# DummyLoad_Frontpanel.net
KiCad netlist of a schematic drawn in EAGLE
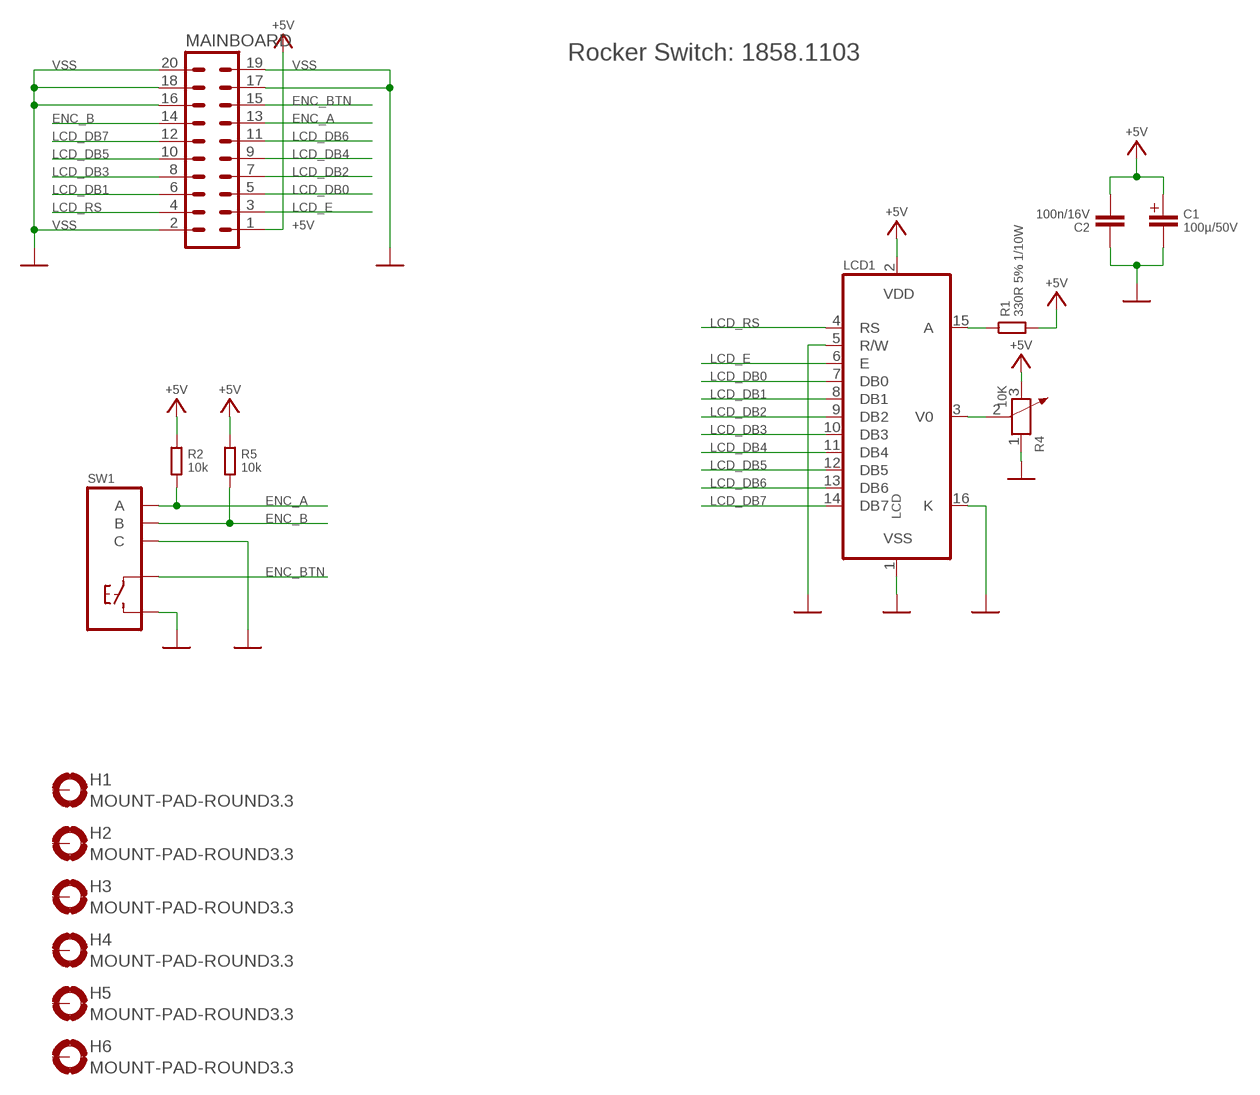
[diagram p0: schematic, sheet 1]

(export (version "E")
  (design (tool "Eeschema 10.0.6"))
  (components
    (comp (ref "C1")
      (value "100µ/50V")
      (footprint "eagle-import:C+_3.5_8")
      (libsource (lib "eagle-import") (part "C+3.5/8"))
    )
    (comp (ref "C2")
      (value "100n/16V")
      (footprint "eagle-import:0805")
      (libsource (lib "eagle-import") (part "CC/0805"))
    )
    (comp (ref "H1")
      (value "MOUNT-PAD-ROUND3.3")
      (footprint "eagle-import:3,3-PAD")
      (libsource (lib "eagle-import") (part "MOUNT-PAD-ROUND3.3"))
    )
    (comp (ref "H2")
      (value "MOUNT-PAD-ROUND3.3")
      (footprint "eagle-import:3,3-PAD")
      (libsource (lib "eagle-import") (part "MOUNT-PAD-ROUND3.3"))
    )
    (comp (ref "H3")
      (value "MOUNT-PAD-ROUND3.3")
      (footprint "eagle-import:3,3-PAD")
      (libsource (lib "eagle-import") (part "MOUNT-PAD-ROUND3.3"))
    )
    (comp (ref "H4")
      (value "MOUNT-PAD-ROUND3.3")
      (footprint "eagle-import:3,3-PAD")
      (libsource (lib "eagle-import") (part "MOUNT-PAD-ROUND3.3"))
    )
    (comp (ref "H5")
      (value "MOUNT-PAD-ROUND3.3")
      (footprint "eagle-import:3,3-PAD")
      (libsource (lib "eagle-import") (part "MOUNT-PAD-ROUND3.3"))
    )
    (comp (ref "H6")
      (value "MOUNT-PAD-ROUND3.3")
      (footprint "eagle-import:3,3-PAD")
      (libsource (lib "eagle-import") (part "MOUNT-PAD-ROUND3.3"))
    )
    (comp (ref "LCD1")
      (value "LCD")
      (footprint "eagle-import:DISPLAYTECH-204C")
      (libsource (lib "eagle-import") (part "LCD"))
    )
    (comp (ref "MAINBOARD")
      (value "MA10-2")
      (footprint "eagle-import:MA10-2")
      (libsource (lib "eagle-import") (part "MA10-2"))
    )
    (comp (ref "R1")
      (value "330R 5% 1/10W")
      (footprint "eagle-import:C0805K")
      (libsource (lib "eagle-import") (part "R-SMD0805"))
    )
    (comp (ref "R2")
      (value "10k")
      (footprint "eagle-import:C0805K")
      (libsource (lib "eagle-import") (part "R-SMD0805"))
    )
    (comp (ref "R4")
      (value "10K")
      (footprint "eagle-import:ADJR3-7.0X7.0X5.0MM")
      (fields (field (name "MPN") "SX3362P"))
      (libsource (lib "eagle-import") (part "TRIMPOT"))
    )
    (comp (ref "R5")
      (value "10k")
      (footprint "eagle-import:C0805K")
      (libsource (lib "eagle-import") (part "R-SMD0805"))
    )
    (comp (ref "SW1")
      (value "EC12E-SW")
      (footprint "eagle-import:EC12E-SW")
      (libsource (lib "eagle-import") (part "EC12E-SW"))
    )
  )
  (nets
    (net (code "1") (name "+5V") (class "Default")
      (node (ref "C1") (pin "+") (pinfunction "+_+") (pintype "passive"))
      (node (ref "C2") (pin "2") (pinfunction "2_2") (pintype "passive"))
      (node (ref "LCD1") (pin "2") (pinfunction "VDD_2") (pintype "power_in"))
      (node (ref "MAINBOARD") (pin "1") (pinfunction "1_1") (pintype "passive"))
      (node (ref "R1") (pin "2") (pinfunction "2_2") (pintype "passive"))
      (node (ref "R2") (pin "1") (pinfunction "1_1") (pintype "passive"))
      (node (ref "R4") (pin "3") (pinfunction "3_3") (pintype "passive"))
      (node (ref "R5") (pin "1") (pinfunction "1_1") (pintype "passive"))
    )
    (net (code "2") (name "/ENC_A") (class "Default")
      (node (ref "MAINBOARD") (pin "13") (pinfunction "13_13") (pintype "passive"))
      (node (ref "R2") (pin "2") (pinfunction "2_2") (pintype "passive"))
      (node (ref "SW1") (pin "A") (pinfunction "A_A") (pintype "passive"))
    )
    (net (code "3") (name "/ENC_B") (class "Default")
      (node (ref "MAINBOARD") (pin "14") (pinfunction "14_14") (pintype "passive"))
      (node (ref "R5") (pin "2") (pinfunction "2_2") (pintype "passive"))
      (node (ref "SW1") (pin "B") (pinfunction "B_B") (pintype "passive"))
    )
    (net (code "4") (name "/ENC_BTN") (class "Default")
      (node (ref "MAINBOARD") (pin "15") (pinfunction "15_15") (pintype "passive"))
      (node (ref "SW1") (pin "1") (pinfunction "1_1") (pintype "passive"))
    )
    (net (code "5") (name "/LCD_DB0") (class "Default")
      (node (ref "LCD1") (pin "7") (pinfunction "DB0_7") (pintype "passive"))
      (node (ref "MAINBOARD") (pin "5") (pinfunction "5_5") (pintype "passive"))
    )
    (net (code "6") (name "/LCD_DB1") (class "Default")
      (node (ref "LCD1") (pin "8") (pinfunction "DB1_8") (pintype "passive"))
      (node (ref "MAINBOARD") (pin "6") (pinfunction "6_6") (pintype "passive"))
    )
    (net (code "7") (name "/LCD_DB2") (class "Default")
      (node (ref "LCD1") (pin "9") (pinfunction "DB2_9") (pintype "passive"))
      (node (ref "MAINBOARD") (pin "7") (pinfunction "7_7") (pintype "passive"))
    )
    (net (code "8") (name "/LCD_DB3") (class "Default")
      (node (ref "LCD1") (pin "10") (pinfunction "DB3_10") (pintype "passive"))
      (node (ref "MAINBOARD") (pin "8") (pinfunction "8_8") (pintype "passive"))
    )
    (net (code "9") (name "/LCD_DB4") (class "Default")
      (node (ref "LCD1") (pin "11") (pinfunction "DB4_11") (pintype "passive"))
      (node (ref "MAINBOARD") (pin "9") (pinfunction "9_9") (pintype "passive"))
    )
    (net (code "10") (name "/LCD_DB5") (class "Default")
      (node (ref "LCD1") (pin "12") (pinfunction "DB5_12") (pintype "passive"))
      (node (ref "MAINBOARD") (pin "10") (pinfunction "10_10") (pintype "passive"))
    )
    (net (code "11") (name "/LCD_DB6") (class "Default")
      (node (ref "LCD1") (pin "13") (pinfunction "DB6_13") (pintype "passive"))
      (node (ref "MAINBOARD") (pin "11") (pinfunction "11_11") (pintype "passive"))
    )
    (net (code "12") (name "/LCD_DB7") (class "Default")
      (node (ref "LCD1") (pin "14") (pinfunction "DB7_14") (pintype "passive"))
      (node (ref "MAINBOARD") (pin "12") (pinfunction "12_12") (pintype "passive"))
    )
    (net (code "13") (name "/LCD_E") (class "Default")
      (node (ref "LCD1") (pin "6") (pinfunction "E_6") (pintype "passive"))
      (node (ref "MAINBOARD") (pin "3") (pinfunction "3_3") (pintype "passive"))
    )
    (net (code "14") (name "/LCD_RS") (class "Default")
      (node (ref "LCD1") (pin "4") (pinfunction "RS_4") (pintype "passive"))
      (node (ref "MAINBOARD") (pin "4") (pinfunction "4_4") (pintype "passive"))
    )
    (net (code "15") (name "Net-(LCD1-A)") (class "Default")
      (node (ref "LCD1") (pin "15") (pinfunction "A_15") (pintype "passive"))
      (node (ref "R1") (pin "1") (pinfunction "1_1") (pintype "passive"))
    )
    (net (code "16") (name "Net-(LCD1-V0)") (class "Default")
      (node (ref "LCD1") (pin "3") (pinfunction "V0_3") (pintype "passive"))
      (node (ref "R4") (pin "2") (pinfunction "2_2") (pintype "passive"))
    )
    (net (code "17") (name "VSS") (class "Default")
      (node (ref "C1") (pin "-") (pinfunction "-_-") (pintype "passive"))
      (node (ref "C2") (pin "1") (pinfunction "1_1") (pintype "passive"))
      (node (ref "LCD1") (pin "1") (pinfunction "VSS_1") (pintype "power_in"))
      (node (ref "LCD1") (pin "16") (pinfunction "K_16") (pintype "passive"))
      (node (ref "LCD1") (pin "5") (pinfunction "R/W_5") (pintype "passive"))
      (node (ref "MAINBOARD") (pin "16") (pinfunction "16_16") (pintype "passive"))
      (node (ref "MAINBOARD") (pin "17") (pinfunction "17_17") (pintype "passive"))
      (node (ref "MAINBOARD") (pin "18") (pinfunction "18_18") (pintype "passive"))
      (node (ref "MAINBOARD") (pin "19") (pinfunction "19_19") (pintype "passive"))
      (node (ref "MAINBOARD") (pin "2") (pinfunction "2_2") (pintype "passive"))
      (node (ref "MAINBOARD") (pin "20") (pinfunction "20_20") (pintype "passive"))
      (node (ref "R4") (pin "1") (pinfunction "1_1") (pintype "passive"))
      (node (ref "SW1") (pin "2") (pinfunction "2_2") (pintype "passive"))
      (node (ref "SW1") (pin "C") (pinfunction "C_C") (pintype "passive"))
    )
    (net (code "18") (name "unconnected-(H1-MOUNT-PadB3,3)") (class "Default")
      (node (ref "H1") (pin "B3,3") (pinfunction "MOUNT_B3,3") (pintype "passive"))
    )
    (net (code "19") (name "unconnected-(H2-MOUNT-PadB3,3)") (class "Default")
      (node (ref "H2") (pin "B3,3") (pinfunction "MOUNT_B3,3") (pintype "passive"))
    )
    (net (code "20") (name "unconnected-(H3-MOUNT-PadB3,3)") (class "Default")
      (node (ref "H3") (pin "B3,3") (pinfunction "MOUNT_B3,3") (pintype "passive"))
    )
    (net (code "21") (name "unconnected-(H4-MOUNT-PadB3,3)") (class "Default")
      (node (ref "H4") (pin "B3,3") (pinfunction "MOUNT_B3,3") (pintype "passive"))
    )
    (net (code "22") (name "unconnected-(H5-MOUNT-PadB3,3)") (class "Default")
      (node (ref "H5") (pin "B3,3") (pinfunction "MOUNT_B3,3") (pintype "passive"))
    )
    (net (code "23") (name "unconnected-(H6-MOUNT-PadB3,3)") (class "Default")
      (node (ref "H6") (pin "B3,3") (pinfunction "MOUNT_B3,3") (pintype "passive"))
    )
  )
)
